# TSOC_CYBLE_R0_2.net
KiCad netlist of a schematic drawn in EAGLE
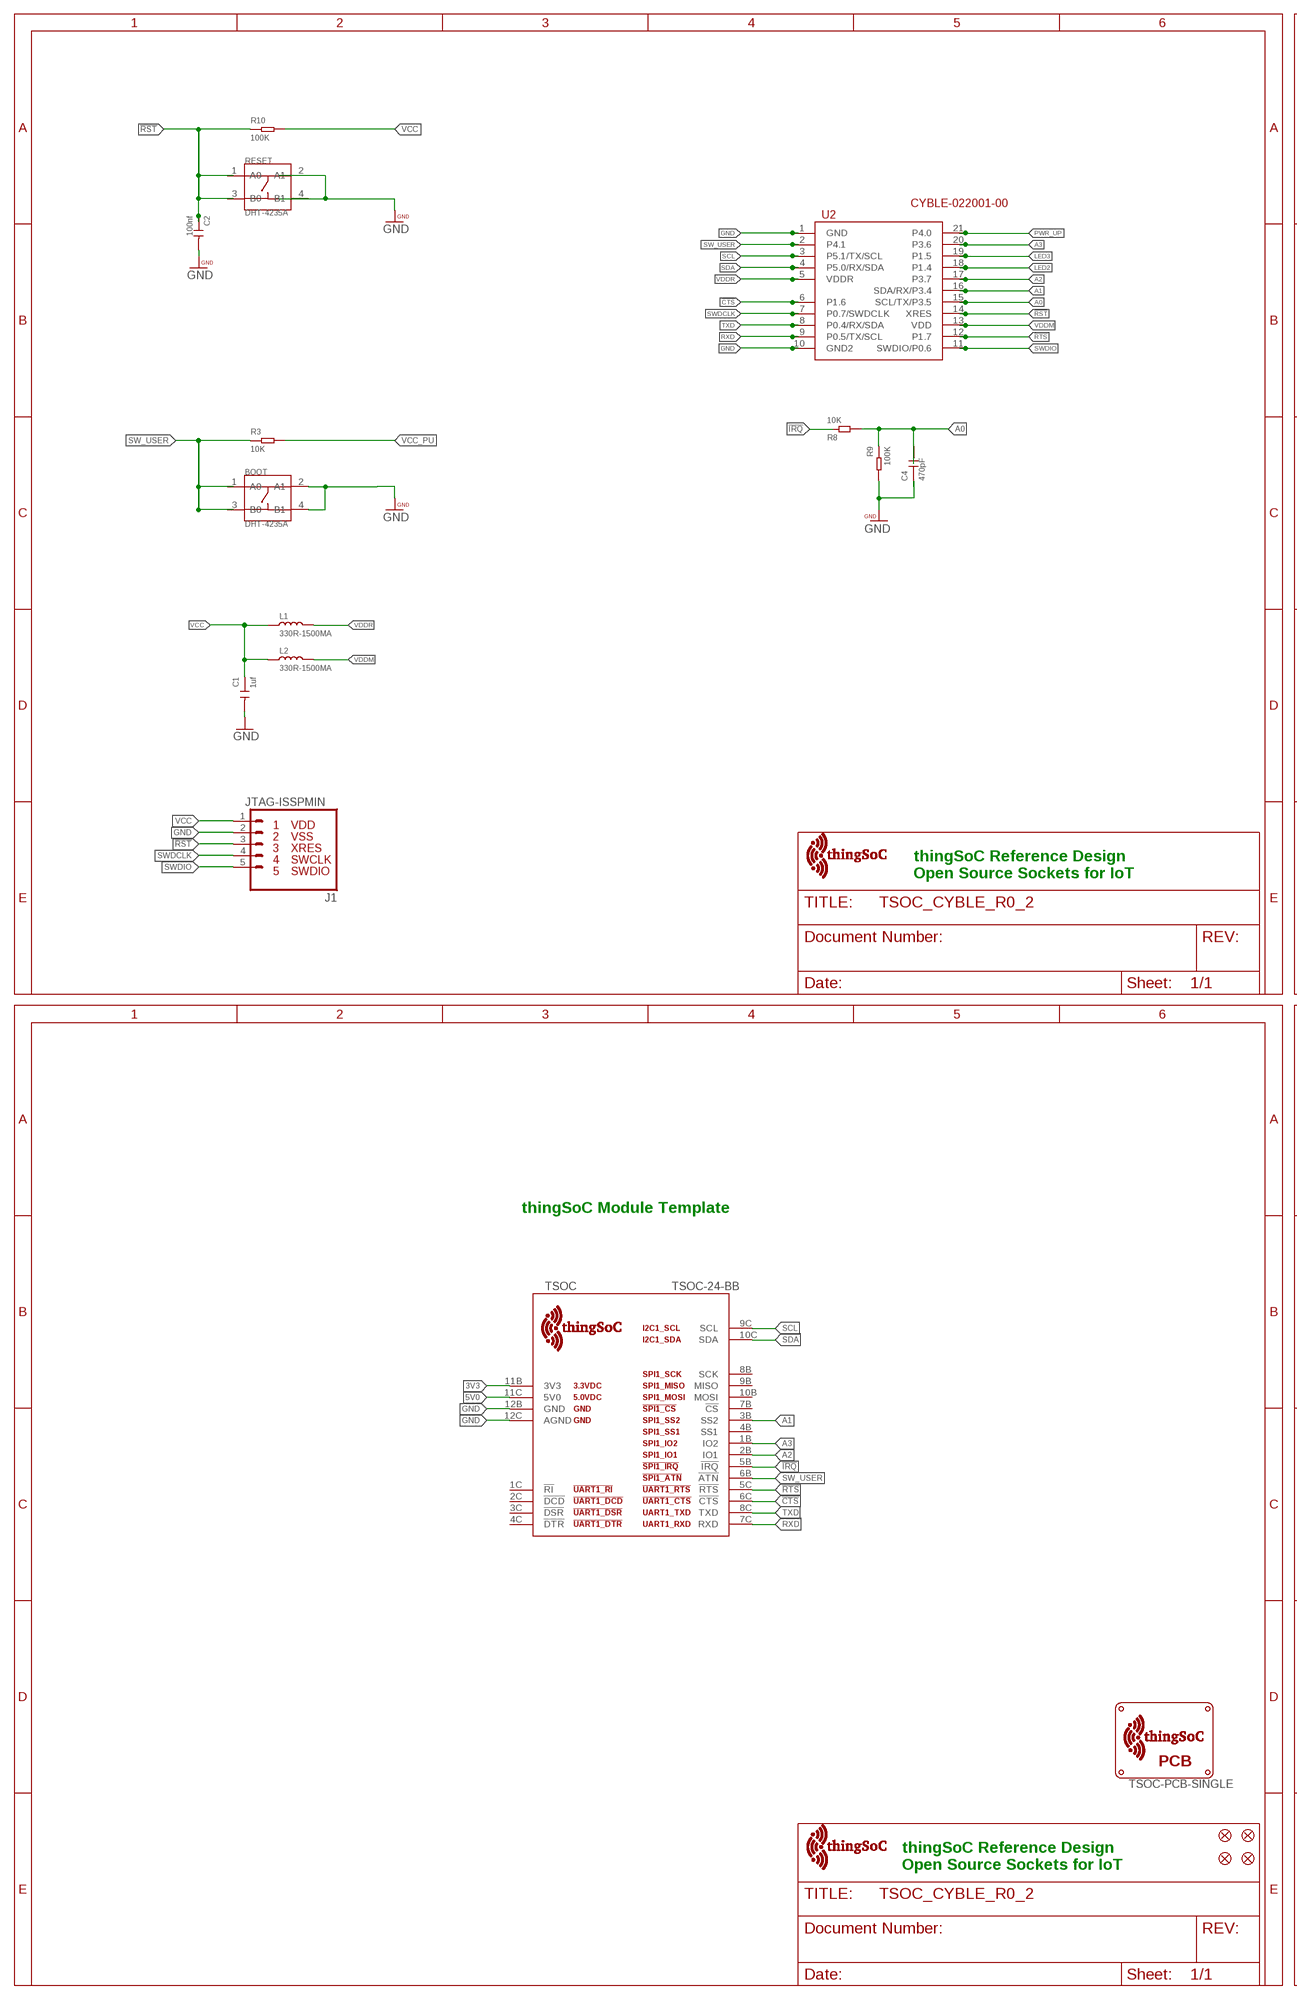
[diagram p0: schematic, sheet 1, part 1 of 2]
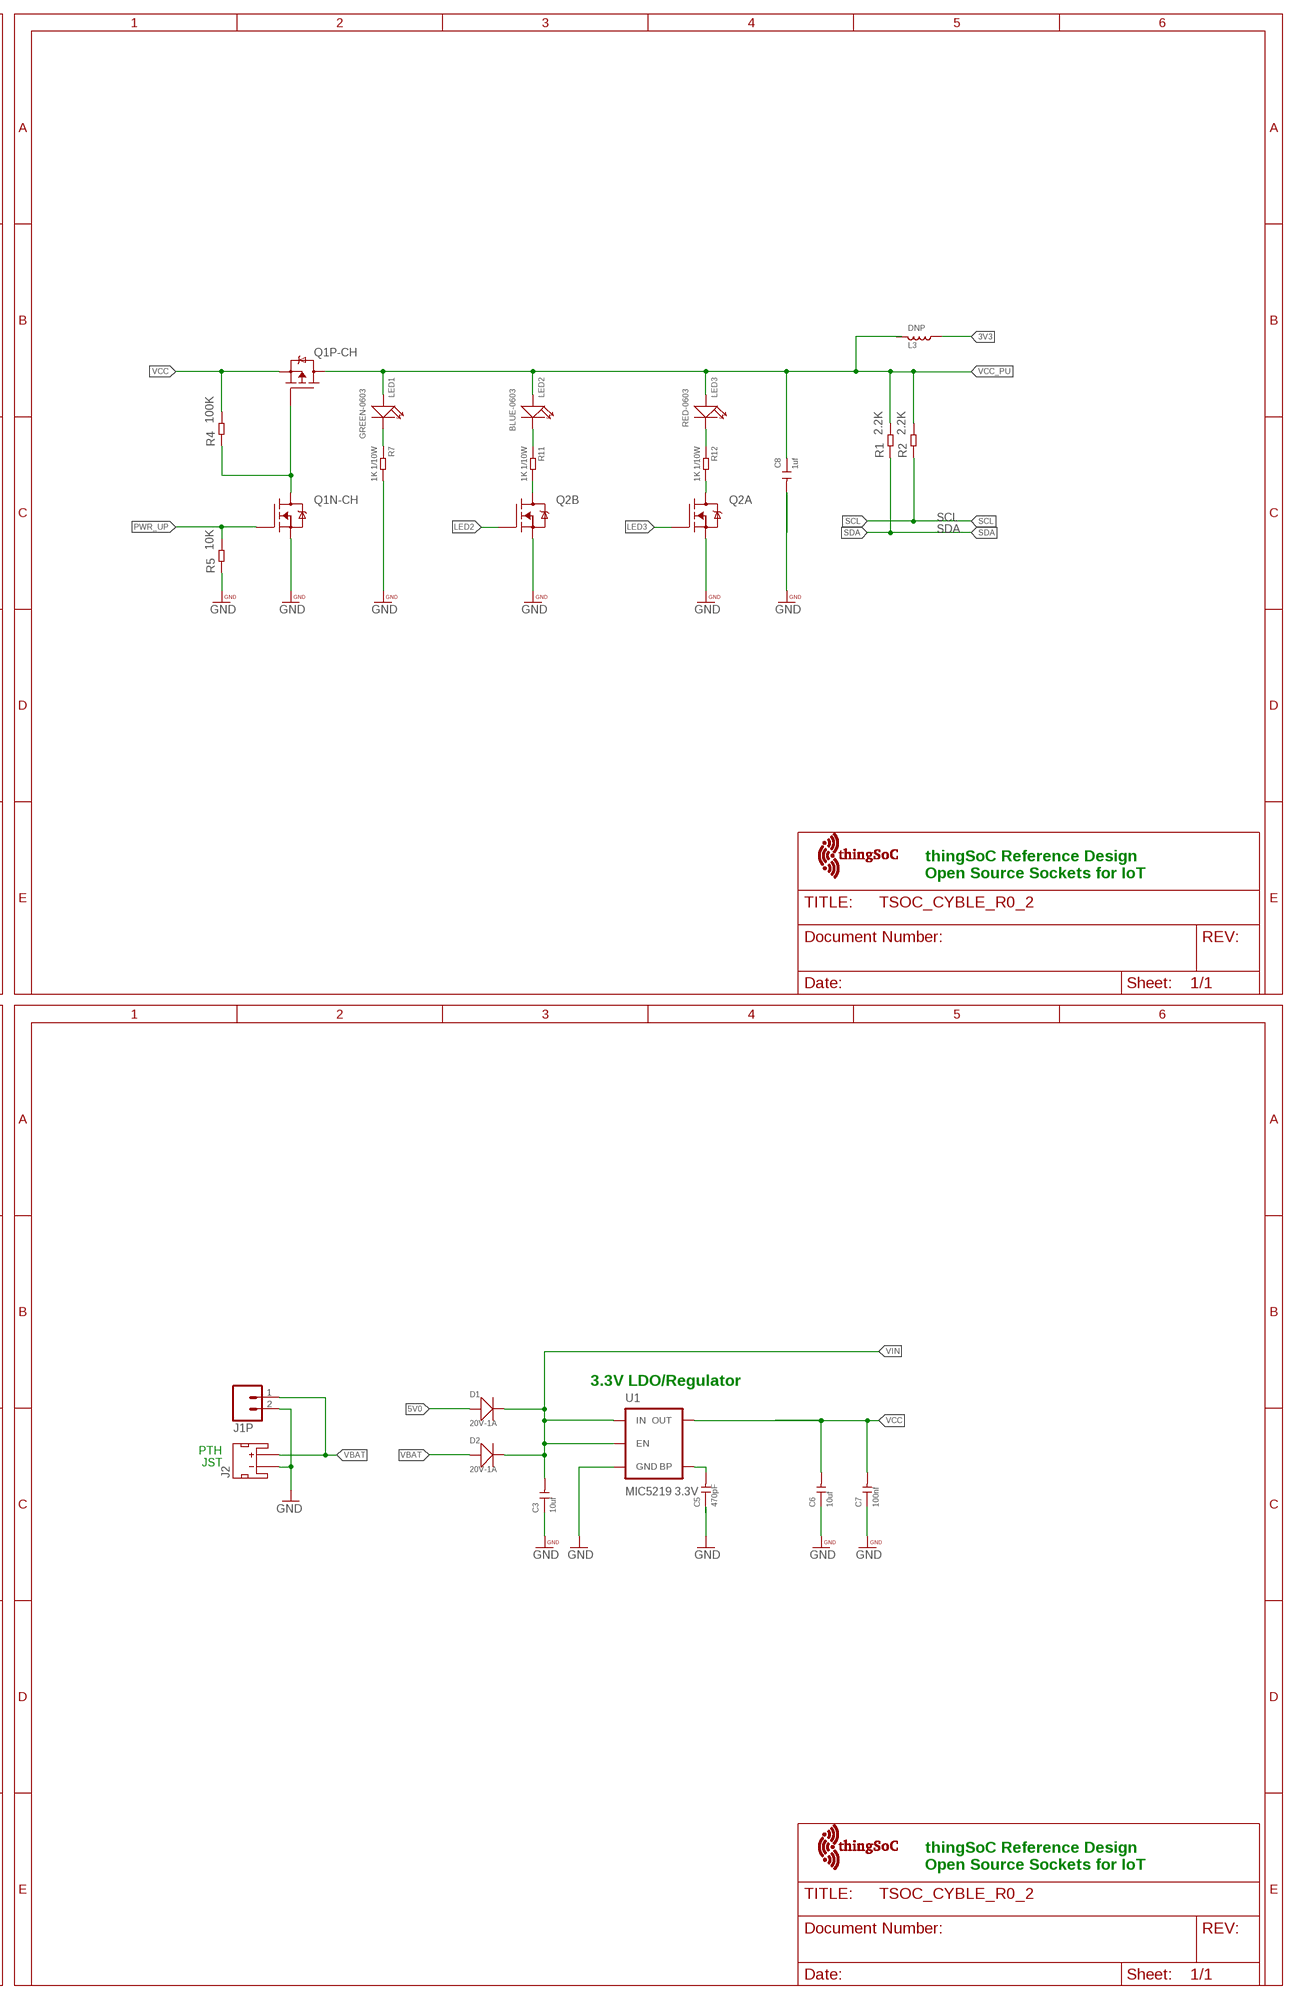
[diagram p1: schematic, sheet 1, part 2 of 2]

(export (version "E")
  (design (tool "Eeschema 10.0.6"))
  (components
    (comp (ref "$$U$1")
      (value "TSOC-LOGO-MED")
      (footprint "eagle-import:TSOC-LOGO-MED")
      (libsource (lib "eagle-import") (part "TSOC-LOGO-MED"))
    )
    (comp (ref "$$U$2")
      (value "TSOC-LOGO-MED")
      (footprint "eagle-import:TSOC-LOGO-MED")
      (libsource (lib "eagle-import") (part "TSOC-LOGO-MED"))
    )
    (comp (ref "BOOT")
      (value "DHT-4235A")
      (footprint "eagle-import:SW4-SMD-4.2X3.2X2.5MM")
      (libsource (lib "eagle-import") (part "SMD-BUTTON-TOP-DHT-4235A(4P-4.2X3.2MM)"))
    )
    (comp (ref "C1")
      (value "1uf")
      (footprint "eagle-import:C0603")
      (fields (field (name "MPN") "CC0603KRX7R8BB105"))
      (libsource (lib "eagle-import") (part "CERAMIC-1UF-25V-10%-X7R(0603)"))
    )
    (comp (ref "C2")
      (value "100nf")
      (footprint "eagle-import:C0603")
      (fields (field (name "MPN") "CC0603KRX7R9BB104"))
      (libsource (lib "eagle-import") (part "CERAMIC-100NF-50V-10%-X7R(0603)"))
    )
    (comp (ref "C3")
      (value "10uf")
      (footprint "eagle-import:C1206")
      (fields (field (name "MPN") "CC1206KKX5R8BB106"))
      (libsource (lib "eagle-import") (part "CERAMIC-10UF-25V-10%-X5R(1206)"))
    )
    (comp (ref "C4")
      (value "470pF")
      (footprint "eagle-import:C0603")
      (fields (field (name "MPN") "CC0603KRX7R9BB104"))
      (libsource (lib "eagle-import") (part "CERAMIC-100NF-50V-10%-X7R(0603)"))
    )
    (comp (ref "C5")
      (value "470pF")
      (footprint "eagle-import:C0603")
      (fields (field (name "MPN") "CC0603KRX7R9BB104"))
      (libsource (lib "eagle-import") (part "CERAMIC-100NF-50V-10%-X7R(0603)"))
    )
    (comp (ref "C6")
      (value "10uf")
      (footprint "eagle-import:C1206")
      (fields (field (name "MPN") "CC1206KKX5R8BB106"))
      (libsource (lib "eagle-import") (part "CERAMIC-10UF-25V-10%-X5R(1206)"))
    )
    (comp (ref "C7")
      (value "100nf")
      (footprint "eagle-import:C0603")
      (fields (field (name "MPN") "CC0603KRX7R9BB104"))
      (libsource (lib "eagle-import") (part "CERAMIC-100NF-50V-10%-X7R(0603)"))
    )
    (comp (ref "C8")
      (value "1uf")
      (footprint "eagle-import:C0603")
      (fields (field (name "MPN") "CC0603KRX7R8BB105"))
      (libsource (lib "eagle-import") (part "CERAMIC-1UF-25V-10%-X7R(0603)"))
    )
    (comp (ref "D1")
      (value "20V-1A")
      (footprint "eagle-import:SOD-123")
      (fields (field (name "MPN") "B5819W"))
      (libsource (lib "eagle-import") (part "SMD-DIODE-SCHOTTKY-20V-1A(SOD-123)"))
    )
    (comp (ref "D2")
      (value "20V-1A")
      (footprint "eagle-import:SOD-123")
      (fields (field (name "MPN") "B5819W"))
      (libsource (lib "eagle-import") (part "SMD-DIODE-SCHOTTKY-20V-1A(SOD-123)"))
    )
    (comp (ref "FID1")
      (value "FIDUCIALUFIDUCIAL")
      (footprint "eagle-import:MICRO-FIDUCIAL")
      (libsource (lib "eagle-import") (part "FIDUCIALUFIDUCIAL"))
    )
    (comp (ref "FID2")
      (value "FIDUCIALUFIDUCIAL")
      (footprint "eagle-import:MICRO-FIDUCIAL")
      (libsource (lib "eagle-import") (part "FIDUCIALUFIDUCIAL"))
    )
    (comp (ref "FID3")
      (value "FIDUCIALUFIDUCIAL")
      (footprint "eagle-import:MICRO-FIDUCIAL")
      (libsource (lib "eagle-import") (part "FIDUCIALUFIDUCIAL"))
    )
    (comp (ref "FID4")
      (value "FIDUCIALUFIDUCIAL")
      (footprint "eagle-import:MICRO-FIDUCIAL")
      (libsource (lib "eagle-import") (part "FIDUCIALUFIDUCIAL"))
    )
    (comp (ref "J1")
      (value "JTAG-ISSPMIN")
      (footprint "eagle-import:PSOC_JTAG_MINSILK")
      (libsource (lib "eagle-import") (part "JTAG-ISSPMIN"))
    )
    (comp (ref "J1P")
      (value "M02-JST-2-PTH-NO_SILK")
      (footprint "eagle-import:JST-2-PTH-NS")
      (libsource (lib "eagle-import") (part "M02-JST-2-PTH-NO_SILK"))
    )
    (comp (ref "J2")
      (value "JST_2MM_MALE")
      (footprint "eagle-import:JST-2-SMD")
      (libsource (lib "eagle-import") (part "JST_2MM_MALE"))
    )
    (comp (ref "L1")
      (value "330R-1500MA")
      (footprint "eagle-import:L0805")
      (fields (field (name "MPN") "BLM21PG331SN1D"))
      (libsource (lib "eagle-import") (part "SMD-FERRITE-BEAD-330R-1500MA(0805)'0805'"))
    )
    (comp (ref "L2")
      (value "330R-1500MA")
      (footprint "eagle-import:L0805")
      (fields (field (name "MPN") "BLM21PG331SN1D"))
      (libsource (lib "eagle-import") (part "SMD-FERRITE-BEAD-330R-1500MA(0805)'0805'"))
    )
    (comp (ref "L3")
      (value "DNP")
      (footprint "eagle-import:L0603")
      (fields (field (name "MPN") "BLM18AG121SN1D"))
      (libsource (lib "eagle-import") (part "SMD-FERRITE-CHIP-120-OHM-500MA(0603)"))
    )
    (comp (ref "LED1")
      (value "GREEN-0603")
      (footprint "eagle-import:LED-0603")
      (fields (field (name "MPN") "19-217-G7C-AN1P2-3T"))
      (libsource (lib "eagle-import") (part "SMD-LED-CLEAR-GREEN(0603)"))
    )
    (comp (ref "LED2")
      (value "BLUE-0603")
      (footprint "eagle-import:LED-0603")
      (fields (field (name "MPN") "19-217-G7C-AN1P2-3T"))
      (libsource (lib "eagle-import") (part "SMD-LED-CLEAR-GREEN(0603)"))
    )
    (comp (ref "LED3")
      (value "RED-0603")
      (footprint "eagle-import:LED-0603")
      (fields (field (name "MPN") "19-217-R6C-AL1M2VY-3T"))
      (libsource (lib "eagle-import") (part "LED-SMD-RED-DIFFUSED(0603)"))
    )
    (comp (ref "PCB")
      (value "TSOC-PCB-SINGLE")
      (footprint "eagle-import:TSOC-BB-BRD-DIM")
      (libsource (lib "eagle-import") (part "TSOC-PCB-SINGLE"))
    )
    (comp (ref "Q1")
      (value "FDC6420C")
      (footprint "eagle-import:SOT95P280X110-6N")
      (libsource (lib "eagle-import") (part "FDC6420C"))
    )
    (comp (ref "Q2")
      (value "FDG1024NZ")
      (footprint "eagle-import:SOT95P280X110-6N")
      (libsource (lib "eagle-import") (part "FDG1024NZ"))
    )
    (comp (ref "R1")
      (value "2.2K")
      (footprint "eagle-import:R0603")
      (fields (field (name "MPN") "RC0603JR-072K2L"))
      (libsource (lib "eagle-import") (part "SMD-RES-2.2K-5%-1/10W(0603)"))
    )
    (comp (ref "R2")
      (value "2.2K")
      (footprint "eagle-import:R0603")
      (fields (field (name "MPN") "RC0603JR-072K2L"))
      (libsource (lib "eagle-import") (part "SMD-RES-2.2K-5%-1/10W(0603)"))
    )
    (comp (ref "R3")
      (value "10K")
      (footprint "eagle-import:R0603")
      (fields (field (name "MPN") "RC0603FR-0710KL"))
      (libsource (lib "eagle-import") (part "SMD-RES-10K-1%-1/10W(0603)"))
    )
    (comp (ref "R4")
      (value "100K")
      (footprint "eagle-import:R0603")
      (fields (field (name "MPN") "RC0603FR-0710KL"))
      (libsource (lib "eagle-import") (part "SMD-RES-10K-1%-1/10W(0603)"))
    )
    (comp (ref "R5")
      (value "10K")
      (footprint "eagle-import:R0603")
      (fields (field (name "MPN") "RC0603FR-0710KL"))
      (libsource (lib "eagle-import") (part "SMD-RES-10K-1%-1/10W(0603)"))
    )
    (comp (ref "R7")
      (value "1K 1/10W")
      (footprint "eagle-import:R0603")
      (fields (field (name "MPN") "RC0603JR-071KL"))
      (libsource (lib "eagle-import") (part "SMD-RES-1K-5%-1/10W(0603)"))
    )
    (comp (ref "R8")
      (value "10K")
      (footprint "eagle-import:R0603")
      (fields (field (name "MPN") "RC0603FR-07100KL"))
      (libsource (lib "eagle-import") (part "SMD-RES-100K-1%-1/10W(0603)"))
    )
    (comp (ref "R9")
      (value "100K")
      (footprint "eagle-import:R0603")
      (fields (field (name "MPN") "RC0603FR-07100KL"))
      (libsource (lib "eagle-import") (part "SMD-RES-100K-1%-1/10W(0603)"))
    )
    (comp (ref "R10")
      (value "100K")
      (footprint "eagle-import:R0603")
      (fields (field (name "MPN") "RC0603FR-0710KL"))
      (libsource (lib "eagle-import") (part "SMD-RES-10K-1%-1/10W(0603)"))
    )
    (comp (ref "R11")
      (value "1K 1/10W")
      (footprint "eagle-import:R0603")
      (fields (field (name "MPN") "RC0603JR-071KL"))
      (libsource (lib "eagle-import") (part "SMD-RES-1K-5%-1/10W(0603)"))
    )
    (comp (ref "R12")
      (value "1K 1/10W")
      (footprint "eagle-import:R0603")
      (fields (field (name "MPN") "RC0603JR-071KL"))
      (libsource (lib "eagle-import") (part "SMD-RES-1K-5%-1/10W(0603)"))
    )
    (comp (ref "RESET")
      (value "DHT-4235A")
      (footprint "eagle-import:SW4-SMD-4.2X3.2X2.5MM")
      (libsource (lib "eagle-import") (part "SMD-BUTTON-TOP-DHT-4235A(4P-4.2X3.2MM)"))
    )
    (comp (ref "TSOC")
      (value "TSOC-24-BB")
      (footprint "eagle-import:TSOC-BB-S24")
      (libsource (lib "eagle-import") (part "TSOC-24-BB"))
    )
    (comp (ref "U$100")
      (value "TSOC-LOGO-MED")
      (footprint "eagle-import:TSOC-LOGO-MED")
      (libsource (lib "eagle-import") (part "TSOC-LOGO-MED"))
    )
    (comp (ref "U$102")
      (value "TSOC-LOGO-MED")
      (footprint "eagle-import:TSOC-LOGO-MED")
      (libsource (lib "eagle-import") (part "TSOC-LOGO-MED"))
    )
    (comp (ref "U1")
      (value "MIC5219 3.3V")
      (footprint "eagle-import:SOT23-5")
      (libsource (lib "eagle-import") (part "V_REG_MIC52193.3V"))
    )
    (comp (ref "U2")
      (value "CYBLE-022001-00")
      (footprint "eagle-import:PROC-BLE-10MM-21")
      (libsource (lib "eagle-import") (part "CYBLE-022001-00"))
    )
  )
  (nets
    (net (code "1") (name "/~{CTS}") (class "Default")
      (node (ref "TSOC") (pin "6C") (pinfunction "~{CTS}_6C") (pintype "bidirectional"))
      (node (ref "U2") (pin "6") (pinfunction "P1.6_6") (pintype "bidirectional"))
    )
    (net (code "2") (name "/~{IRQ}") (class "Default")
      (node (ref "R8") (pin "1") (pinfunction "1_1") (pintype "passive"))
      (node (ref "TSOC") (pin "5B") (pinfunction "~{IRQ}_5B") (pintype "bidirectional"))
    )
    (net (code "3") (name "/~{RST}") (class "Default")
      (node (ref "C2") (pin "1") (pinfunction "1_1") (pintype "passive"))
      (node (ref "J1") (pin "3") (pinfunction "3_3") (pintype "passive"))
      (node (ref "R10") (pin "1") (pinfunction "1_1") (pintype "passive"))
      (node (ref "RESET") (pin "1") (pinfunction "A0_1") (pintype "bidirectional"))
      (node (ref "RESET") (pin "3") (pinfunction "B0_3") (pintype "bidirectional"))
      (node (ref "U2") (pin "14") (pinfunction "XRES_14") (pintype "input"))
    )
    (net (code "4") (name "/~{RTS}") (class "Default")
      (node (ref "TSOC") (pin "5C") (pinfunction "~{RTS}_5C") (pintype "bidirectional"))
      (node (ref "U2") (pin "12") (pinfunction "P1.7_12") (pintype "bidirectional"))
    )
    (net (code "5") (name "3V3") (class "Default")
      (node (ref "L3") (pin "2") (pinfunction "2_2") (pintype "passive"))
      (node (ref "TSOC") (pin "11B") (pinfunction "3V3_11B") (pintype "bidirectional"))
    )
    (net (code "6") (name "5V0") (class "Default")
      (node (ref "D1") (pin "+") (pinfunction "+_+") (pintype "passive"))
      (node (ref "TSOC") (pin "11C") (pinfunction "5V0_11C") (pintype "bidirectional"))
    )
    (net (code "7") (name "A0") (class "Default")
      (node (ref "C4") (pin "2") (pinfunction "2_2") (pintype "passive"))
      (node (ref "R8") (pin "2") (pinfunction "2_2") (pintype "passive"))
      (node (ref "R9") (pin "1") (pinfunction "1_1") (pintype "passive"))
      (node (ref "U2") (pin "15") (pinfunction "SCL/TX/P3.5_15") (pintype "bidirectional"))
    )
    (net (code "8") (name "A1") (class "Default")
      (node (ref "TSOC") (pin "3B") (pinfunction "SS2_3B") (pintype "bidirectional"))
      (node (ref "U2") (pin "16") (pinfunction "SDA/RX/P3.4_16") (pintype "bidirectional"))
    )
    (net (code "9") (name "A2") (class "Default")
      (node (ref "TSOC") (pin "2B") (pinfunction "IO1_2B") (pintype "bidirectional"))
      (node (ref "U2") (pin "17") (pinfunction "P3.7_17") (pintype "bidirectional"))
    )
    (net (code "10") (name "A3") (class "Default")
      (node (ref "TSOC") (pin "1B") (pinfunction "IO2_1B") (pintype "bidirectional"))
      (node (ref "U2") (pin "20") (pinfunction "P3.6_20") (pintype "bidirectional"))
    )
    (net (code "11") (name "GND") (class "Default")
      (node (ref "BOOT") (pin "2") (pinfunction "A1_2") (pintype "bidirectional"))
      (node (ref "BOOT") (pin "4") (pinfunction "B1_4") (pintype "bidirectional"))
      (node (ref "C1") (pin "2") (pinfunction "2_2") (pintype "passive"))
      (node (ref "C2") (pin "2") (pinfunction "2_2") (pintype "passive"))
      (node (ref "C3") (pin "1") (pinfunction "1_1") (pintype "passive"))
      (node (ref "C4") (pin "1") (pinfunction "1_1") (pintype "passive"))
      (node (ref "C5") (pin "1") (pinfunction "1_1") (pintype "passive"))
      (node (ref "C6") (pin "1") (pinfunction "1_1") (pintype "passive"))
      (node (ref "C7") (pin "1") (pinfunction "1_1") (pintype "passive"))
      (node (ref "C8") (pin "2") (pinfunction "2_2") (pintype "passive"))
      (node (ref "J1") (pin "2") (pinfunction "2_2") (pintype "passive"))
      (node (ref "J1P") (pin "2") (pinfunction "2_2") (pintype "passive"))
      (node (ref "J2") (pin "1") (pinfunction "-_1") (pintype "bidirectional"))
      (node (ref "Q1") (pin "5") (pinfunction "S_5") (pintype "passive"))
      (node (ref "Q2") (pin "1") (pinfunction "S_1") (pintype "passive"))
      (node (ref "Q2") (pin "4") (pinfunction "S_4") (pintype "passive"))
      (node (ref "R5") (pin "1") (pinfunction "1_1") (pintype "passive"))
      (node (ref "R7") (pin "2") (pinfunction "2_2") (pintype "passive"))
      (node (ref "R9") (pin "2") (pinfunction "2_2") (pintype "passive"))
      (node (ref "RESET") (pin "2") (pinfunction "A1_2") (pintype "bidirectional"))
      (node (ref "RESET") (pin "4") (pinfunction "B1_4") (pintype "bidirectional"))
      (node (ref "TSOC") (pin "12B") (pinfunction "GND_12B") (pintype "bidirectional"))
      (node (ref "TSOC") (pin "12C") (pinfunction "AGND_12C") (pintype "bidirectional"))
      (node (ref "U1") (pin "2") (pinfunction "GND_2") (pintype "input"))
      (node (ref "U2") (pin "1") (pinfunction "GND_1") (pintype "power_in"))
      (node (ref "U2") (pin "10") (pinfunction "GND2_10") (pintype "power_in"))
    )
    (net (code "12") (name "LED2") (class "Default")
      (node (ref "Q2") (pin "5") (pinfunction "G_5") (pintype "passive"))
      (node (ref "U2") (pin "18") (pinfunction "P1.4_18") (pintype "bidirectional"))
    )
    (net (code "13") (name "LED3") (class "Default")
      (node (ref "Q2") (pin "2") (pinfunction "G_2") (pintype "passive"))
      (node (ref "U2") (pin "19") (pinfunction "P1.5_19") (pintype "bidirectional"))
    )
    (net (code "14") (name "Net-(LED1-Pad-)") (class "Default")
      (node (ref "LED1") (pin "-") (pinfunction "-_-") (pintype "passive"))
      (node (ref "R7") (pin "1") (pinfunction "1_1") (pintype "passive"))
    )
    (net (code "15") (name "Net-(LED2-Pad-)") (class "Default")
      (node (ref "LED2") (pin "-") (pinfunction "-_-") (pintype "passive"))
      (node (ref "R11") (pin "1") (pinfunction "1_1") (pintype "passive"))
    )
    (net (code "16") (name "Net-(LED3-Pad-)") (class "Default")
      (node (ref "LED3") (pin "-") (pinfunction "-_-") (pintype "passive"))
      (node (ref "R12") (pin "1") (pinfunction "1_1") (pintype "passive"))
    )
    (net (code "17") (name "Net-(Q1A-D)") (class "Default")
      (node (ref "Q1") (pin "3") (pinfunction "G_3") (pintype "passive"))
      (node (ref "Q1") (pin "6") (pinfunction "D_6") (pintype "passive"))
      (node (ref "R4") (pin "1") (pinfunction "1_1") (pintype "passive"))
    )
    (net (code "18") (name "Net-(Q2A-D)") (class "Default")
      (node (ref "Q2") (pin "6") (pinfunction "D_6") (pintype "passive"))
      (node (ref "R12") (pin "2") (pinfunction "2_2") (pintype "passive"))
    )
    (net (code "19") (name "Net-(Q2B-D)") (class "Default")
      (node (ref "Q2") (pin "3") (pinfunction "D_3") (pintype "passive"))
      (node (ref "R11") (pin "2") (pinfunction "2_2") (pintype "passive"))
    )
    (net (code "20") (name "Net-(U1-BP)") (class "Default")
      (node (ref "C5") (pin "2") (pinfunction "2_2") (pintype "passive"))
      (node (ref "U1") (pin "4") (pinfunction "BP_4") (pintype "input"))
    )
    (net (code "21") (name "PWR_UP") (class "Default")
      (node (ref "Q1") (pin "1") (pinfunction "G_1") (pintype "passive"))
      (node (ref "R5") (pin "2") (pinfunction "2_2") (pintype "passive"))
      (node (ref "U2") (pin "21") (pinfunction "P4.0_21") (pintype "bidirectional"))
    )
    (net (code "22") (name "RXD") (class "Default")
      (node (ref "TSOC") (pin "7C") (pinfunction "RXD_7C") (pintype "bidirectional"))
      (node (ref "U2") (pin "9") (pinfunction "P0.5/TX/SCL_9") (pintype "bidirectional"))
    )
    (net (code "23") (name "SCL") (class "Default")
      (node (ref "R2") (pin "1") (pinfunction "1_1") (pintype "passive"))
      (node (ref "TSOC") (pin "9C") (pinfunction "SCL_9C") (pintype "bidirectional"))
      (node (ref "U2") (pin "3") (pinfunction "P5.1/TX/SCL_3") (pintype "bidirectional"))
    )
    (net (code "24") (name "SDA") (class "Default")
      (node (ref "R1") (pin "1") (pinfunction "1_1") (pintype "passive"))
      (node (ref "TSOC") (pin "10C") (pinfunction "SDA_10C") (pintype "bidirectional"))
      (node (ref "U2") (pin "4") (pinfunction "P5.0/RX/SDA_4") (pintype "bidirectional"))
    )
    (net (code "25") (name "SWDCLK") (class "Default")
      (node (ref "J1") (pin "4") (pinfunction "4_4") (pintype "passive"))
      (node (ref "U2") (pin "7") (pinfunction "P0.7/SWDCLK_7") (pintype "bidirectional"))
    )
    (net (code "26") (name "SWDIO") (class "Default")
      (node (ref "J1") (pin "5") (pinfunction "5_5") (pintype "passive"))
      (node (ref "U2") (pin "11") (pinfunction "SWDIO/P0.6_11") (pintype "bidirectional"))
    )
    (net (code "27") (name "SW_USER") (class "Default")
      (node (ref "BOOT") (pin "1") (pinfunction "A0_1") (pintype "bidirectional"))
      (node (ref "BOOT") (pin "3") (pinfunction "B0_3") (pintype "bidirectional"))
      (node (ref "R3") (pin "1") (pinfunction "1_1") (pintype "passive"))
      (node (ref "TSOC") (pin "6B") (pinfunction "~{ATN}_6B") (pintype "bidirectional"))
      (node (ref "U2") (pin "2") (pinfunction "P4.1_2") (pintype "bidirectional"))
    )
    (net (code "28") (name "TXD") (class "Default")
      (node (ref "TSOC") (pin "8C") (pinfunction "TXD_8C") (pintype "bidirectional"))
      (node (ref "U2") (pin "8") (pinfunction "P0.4/RX/SDA_8") (pintype "bidirectional"))
    )
    (net (code "29") (name "VBAT") (class "Default")
      (node (ref "D2") (pin "+") (pinfunction "+_+") (pintype "passive"))
      (node (ref "J1P") (pin "1") (pinfunction "1_1") (pintype "passive"))
      (node (ref "J2") (pin "2") (pinfunction "+_2") (pintype "bidirectional"))
    )
    (net (code "30") (name "VCC") (class "Default")
      (node (ref "C1") (pin "1") (pinfunction "1_1") (pintype "passive"))
      (node (ref "C6") (pin "2") (pinfunction "2_2") (pintype "passive"))
      (node (ref "C7") (pin "2") (pinfunction "2_2") (pintype "passive"))
      (node (ref "J1") (pin "1") (pinfunction "1_1") (pintype "passive"))
      (node (ref "L1") (pin "1") (pinfunction "1_1") (pintype "passive"))
      (node (ref "L2") (pin "1") (pinfunction "1_1") (pintype "passive"))
      (node (ref "Q1") (pin "2") (pinfunction "S_2") (pintype "passive"))
      (node (ref "R10") (pin "2") (pinfunction "2_2") (pintype "passive"))
      (node (ref "R4") (pin "2") (pinfunction "2_2") (pintype "passive"))
      (node (ref "U1") (pin "5") (pinfunction "OUT_5") (pintype "passive"))
    )
    (net (code "31") (name "VCC_PU") (class "Default")
      (node (ref "C8") (pin "1") (pinfunction "1_1") (pintype "passive"))
      (node (ref "L3") (pin "1") (pinfunction "1_1") (pintype "passive"))
      (node (ref "LED1") (pin "+") (pinfunction "+_+") (pintype "passive"))
      (node (ref "LED2") (pin "+") (pinfunction "+_+") (pintype "passive"))
      (node (ref "LED3") (pin "+") (pinfunction "+_+") (pintype "passive"))
      (node (ref "Q1") (pin "4") (pinfunction "D_4") (pintype "passive"))
      (node (ref "R1") (pin "2") (pinfunction "2_2") (pintype "passive"))
      (node (ref "R2") (pin "2") (pinfunction "2_2") (pintype "passive"))
      (node (ref "R3") (pin "2") (pinfunction "2_2") (pintype "passive"))
    )
    (net (code "32") (name "VDDM") (class "Default")
      (node (ref "L2") (pin "2") (pinfunction "2_2") (pintype "passive"))
      (node (ref "U2") (pin "13") (pinfunction "VDD_13") (pintype "power_in"))
    )
    (net (code "33") (name "VDDR") (class "Default")
      (node (ref "L1") (pin "2") (pinfunction "2_2") (pintype "passive"))
      (node (ref "U2") (pin "5") (pinfunction "VDDR_5") (pintype "power_in"))
    )
    (net (code "34") (name "VIN") (class "Default")
      (node (ref "C3") (pin "2") (pinfunction "2_2") (pintype "passive"))
      (node (ref "D1") (pin "-") (pinfunction "-_-") (pintype "passive"))
      (node (ref "D2") (pin "-") (pinfunction "-_-") (pintype "passive"))
      (node (ref "U1") (pin "1") (pinfunction "IN_1") (pintype "input"))
      (node (ref "U1") (pin "3") (pinfunction "EN_3") (pintype "input"))
    )
    (net (code "35") (name "unconnected-(J2-PAD1-PadNC1)") (class "Default")
      (node (ref "J2") (pin "NC1") (pinfunction "PAD1_NC1") (pintype "bidirectional"))
    )
    (net (code "36") (name "unconnected-(J2-PAD2-PadNC2)") (class "Default")
      (node (ref "J2") (pin "NC2") (pinfunction "PAD2_NC2") (pintype "bidirectional"))
    )
    (net (code "37") (name "unconnected-(TSOC-MISO-Pad9B)") (class "Default")
      (node (ref "TSOC") (pin "9B") (pinfunction "MISO_9B") (pintype "bidirectional"))
    )
    (net (code "38") (name "unconnected-(TSOC-MOSI-Pad10B)") (class "Default")
      (node (ref "TSOC") (pin "10B") (pinfunction "MOSI_10B") (pintype "bidirectional"))
    )
    (net (code "39") (name "unconnected-(TSOC-SCK-Pad8B)") (class "Default")
      (node (ref "TSOC") (pin "8B") (pinfunction "SCK_8B") (pintype "bidirectional"))
    )
    (net (code "40") (name "unconnected-(TSOC-SS1-Pad4B)") (class "Default")
      (node (ref "TSOC") (pin "4B") (pinfunction "SS1_4B") (pintype "bidirectional"))
    )
    (net (code "41") (name "unconnected-(TSOC-~{CS}-Pad7B)") (class "Default")
      (node (ref "TSOC") (pin "7B") (pinfunction "~{CS}_7B") (pintype "bidirectional"))
    )
    (net (code "42") (name "unconnected-(TSOC-~{DCD}-Pad2C)") (class "Default")
      (node (ref "TSOC") (pin "2C") (pinfunction "~{DCD}_2C") (pintype "bidirectional"))
    )
    (net (code "43") (name "unconnected-(TSOC-~{DSR}-Pad3C)") (class "Default")
      (node (ref "TSOC") (pin "3C") (pinfunction "~{DSR}_3C") (pintype "bidirectional"))
    )
    (net (code "44") (name "unconnected-(TSOC-~{DTR}-Pad4C)") (class "Default")
      (node (ref "TSOC") (pin "4C") (pinfunction "~{DTR}_4C") (pintype "bidirectional"))
    )
    (net (code "45") (name "unconnected-(TSOC-~{RI}-Pad1C)") (class "Default")
      (node (ref "TSOC") (pin "1C") (pinfunction "~{RI}_1C") (pintype "bidirectional"))
    )
  )
)
